# kritzler_shield.net
KiCad netlist of a schematic drawn in EAGLE
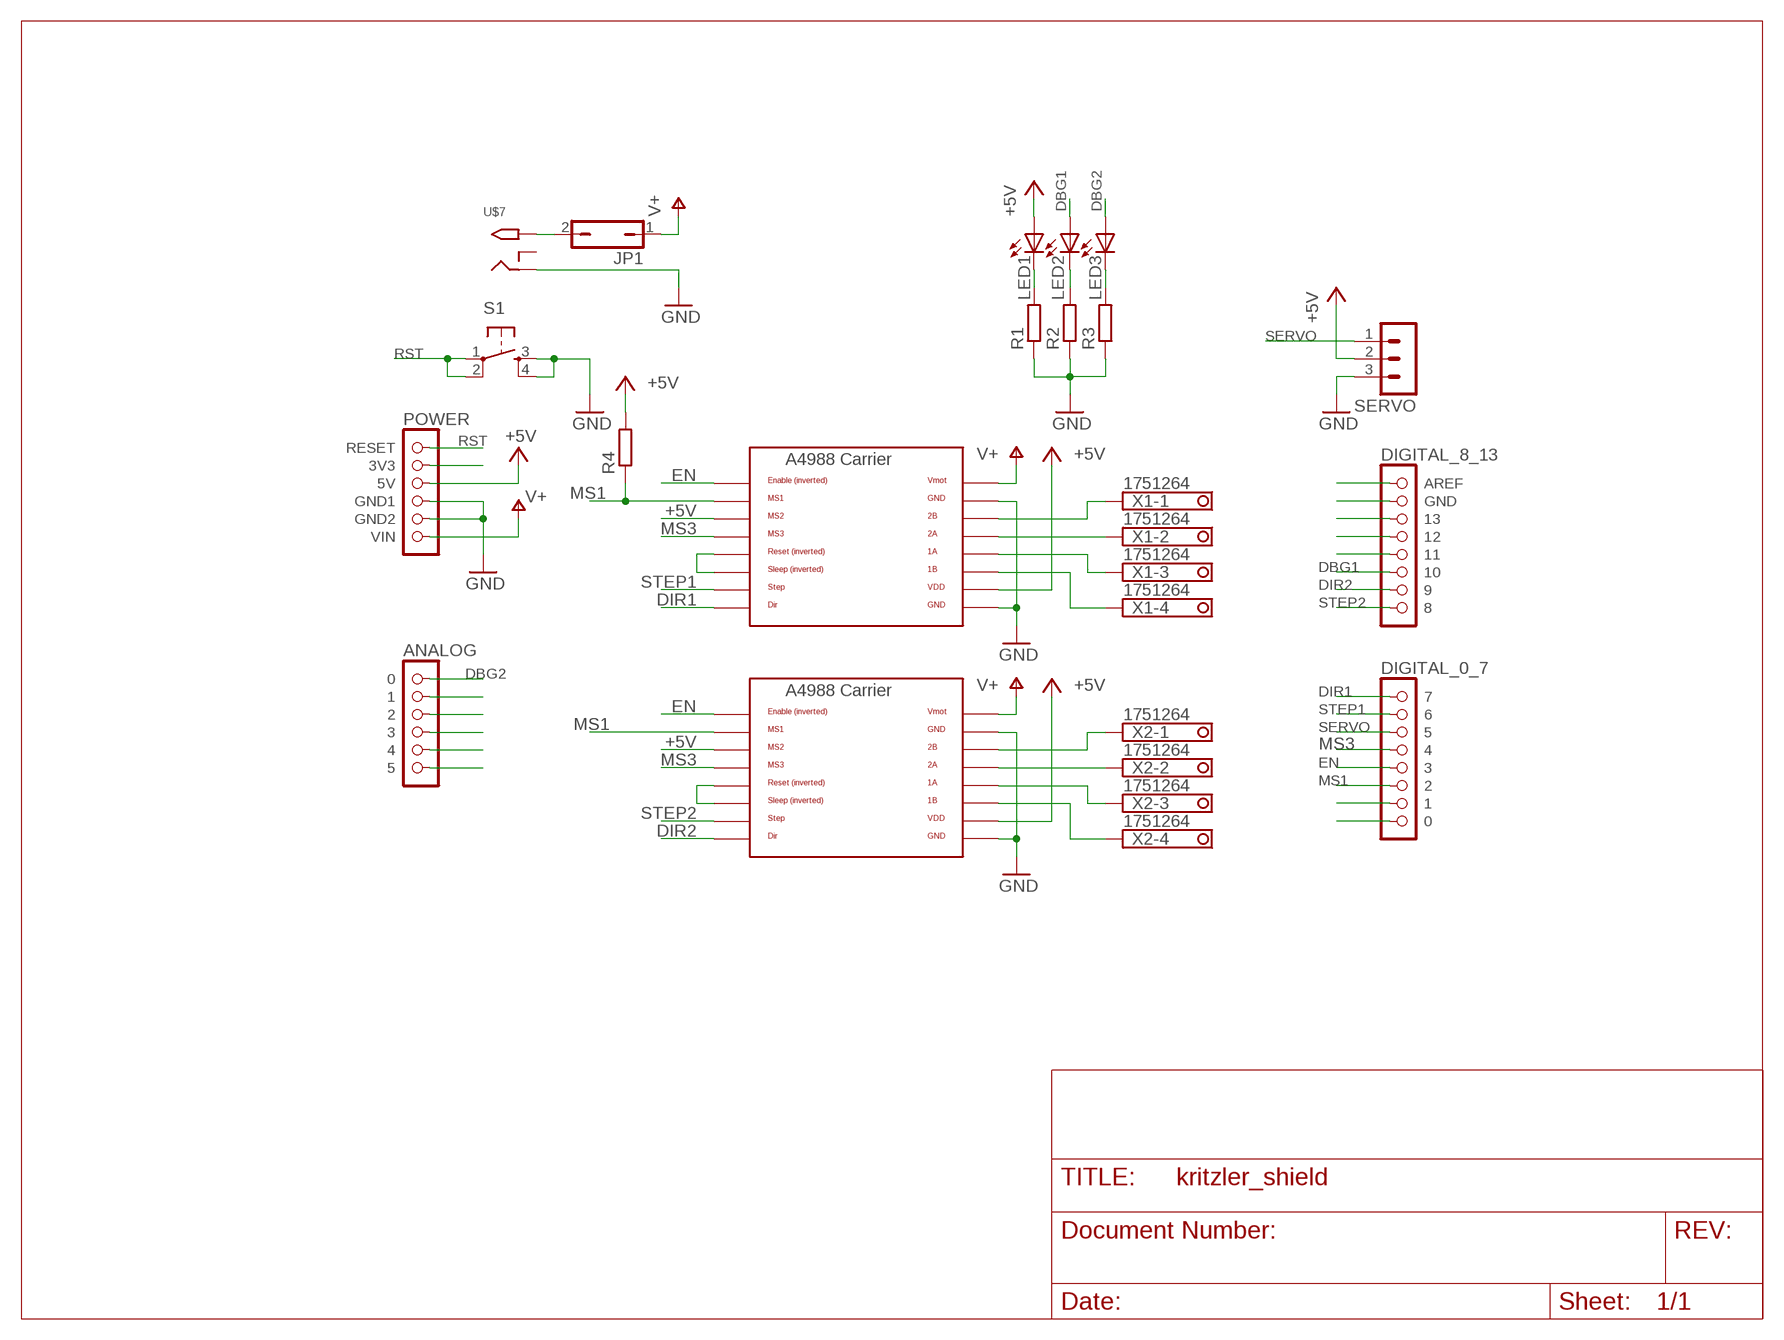
[diagram p0: schematic, sheet 1]

(export (version "E")
  (design (tool "Eeschema 10.0.6"))
  (components
    (comp (ref "JP1")
      (value "JP1Q")
      (footprint "eagle-import:JP1")
      (libsource (lib "eagle-import") (part "JP1Q"))
    )
    (comp (ref "LED1")
      (value "LED5MM")
      (footprint "eagle-import:LED5MM")
      (libsource (lib "eagle-import") (part "LED5MM"))
    )
    (comp (ref "LED2")
      (value "LED5MM")
      (footprint "eagle-import:LED5MM")
      (libsource (lib "eagle-import") (part "LED5MM"))
    )
    (comp (ref "LED3")
      (value "LED5MM")
      (footprint "eagle-import:LED5MM")
      (libsource (lib "eagle-import") (part "LED5MM"))
    )
    (comp (ref "R1")
      (value "R-EU_0207/10")
      (footprint "eagle-import:0207_10")
      (libsource (lib "eagle-import") (part "R-EU_0207/10"))
    )
    (comp (ref "R2")
      (value "R-EU_0207/10")
      (footprint "eagle-import:0207_10")
      (libsource (lib "eagle-import") (part "R-EU_0207/10"))
    )
    (comp (ref "R3")
      (value "R-EU_0207/10")
      (footprint "eagle-import:0207_10")
      (libsource (lib "eagle-import") (part "R-EU_0207/10"))
    )
    (comp (ref "R4")
      (value "R-EU_0207/10")
      (footprint "eagle-import:0207_10")
      (libsource (lib "eagle-import") (part "R-EU_0207/10"))
    )
    (comp (ref "S1")
      (value "TAC_SWITCHPTH")
      (footprint "eagle-import:TACTILE-PTH")
      (libsource (lib "eagle-import") (part "TAC_SWITCHPTH"))
    )
    (comp (ref "SERVO")
      (value "MA03-1")
      (footprint "eagle-import:MA03-1")
      (libsource (lib "eagle-import") (part "MA03-1"))
    )
    (comp (ref "U$1")
      (value "POWER")
      (footprint "eagle-import:1X06")
      (libsource (lib "eagle-import") (part "POWER"))
    )
    (comp (ref "U$2")
      (value "ANALOG")
      (footprint "eagle-import:1X06")
      (libsource (lib "eagle-import") (part "ANALOG"))
    )
    (comp (ref "U$3")
      (value "DIGITAL_0_7")
      (footprint "eagle-import:1X08")
      (libsource (lib "eagle-import") (part "DIGITAL_0_7"))
    )
    (comp (ref "U$4")
      (value "DIGITAL_8_13")
      (footprint "eagle-import:1X08")
      (libsource (lib "eagle-import") (part "DIGITAL_8_13"))
    )
    (comp (ref "U$5")
      (value "A4988BREAKOUT")
      (footprint "eagle-import:A4988BREAKOUT")
      (libsource (lib "eagle-import") (part "A4988BREAKOUT"))
    )
    (comp (ref "U$6")
      (value "A4988BREAKOUT")
      (footprint "eagle-import:A4988BREAKOUT")
      (libsource (lib "eagle-import") (part "A4988BREAKOUT"))
    )
    (comp (ref "U$7")
      (value "2.1MMJACKTHM")
      (footprint "eagle-import:PJ-102A")
      (libsource (lib "eagle-import") (part "2.1MMJACKTHM"))
    )
    (comp (ref "X1")
      (value "1751264")
      (footprint "eagle-import:1751264")
      (libsource (lib "eagle-import") (part "1751264"))
    )
    (comp (ref "X2")
      (value "1751264")
      (footprint "eagle-import:1751264")
      (libsource (lib "eagle-import") (part "1751264"))
    )
  )
  (nets
    (net (code "1") (name "+5V") (class "Default")
      (node (ref "LED1") (pin "A") (pinfunction "A_A") (pintype "passive"))
      (node (ref "R4") (pin "2") (pinfunction "2_2") (pintype "passive"))
      (node (ref "SERVO") (pin "2") (pinfunction "2_2") (pintype "passive"))
      (node (ref "U$1") (pin "3") (pinfunction "5V_3") (pintype "passive"))
      (node (ref "U$5") (pin "MS2") (pinfunction "MS2_MS2") (pintype "input"))
      (node (ref "U$5") (pin "VDD") (pinfunction "VDD_VDD") (pintype "power_in"))
      (node (ref "U$6") (pin "MS2") (pinfunction "MS2_MS2") (pintype "input"))
      (node (ref "U$6") (pin "VDD") (pinfunction "VDD_VDD") (pintype "power_in"))
    )
    (net (code "2") (name "/DBG1") (class "Default")
      (node (ref "LED2") (pin "A") (pinfunction "A_A") (pintype "passive"))
      (node (ref "U$4") (pin "6") (pinfunction "10_6") (pintype "passive"))
    )
    (net (code "3") (name "/DBG2") (class "Default")
      (node (ref "LED3") (pin "A") (pinfunction "A_A") (pintype "passive"))
      (node (ref "U$2") (pin "1") (pinfunction "0_1") (pintype "passive"))
    )
    (net (code "4") (name "/DIR1") (class "Default")
      (node (ref "U$3") (pin "1") (pinfunction "7_1") (pintype "passive"))
      (node (ref "U$5") (pin "DIR") (pinfunction "DIR_DIR") (pintype "input"))
    )
    (net (code "5") (name "/DIR2") (class "Default")
      (node (ref "U$4") (pin "7") (pinfunction "9_7") (pintype "passive"))
      (node (ref "U$6") (pin "DIR") (pinfunction "DIR_DIR") (pintype "input"))
    )
    (net (code "6") (name "/EN") (class "Default")
      (node (ref "U$3") (pin "5") (pinfunction "3_5") (pintype "passive"))
      (node (ref "U$5") (pin "EN") (pinfunction "EN_EN") (pintype "input"))
      (node (ref "U$6") (pin "EN") (pinfunction "EN_EN") (pintype "input"))
    )
    (net (code "7") (name "/MS1") (class "Default")
      (node (ref "R4") (pin "1") (pinfunction "1_1") (pintype "passive"))
      (node (ref "U$3") (pin "6") (pinfunction "2_6") (pintype "passive"))
      (node (ref "U$5") (pin "MS1") (pinfunction "MS1_MS1") (pintype "input"))
      (node (ref "U$6") (pin "MS1") (pinfunction "MS1_MS1") (pintype "input"))
    )
    (net (code "8") (name "/MS3") (class "Default")
      (node (ref "U$3") (pin "4") (pinfunction "4_4") (pintype "passive"))
      (node (ref "U$5") (pin "MS3") (pinfunction "MS3_MS3") (pintype "input"))
      (node (ref "U$6") (pin "MS3") (pinfunction "MS3_MS3") (pintype "input"))
    )
    (net (code "9") (name "/RST") (class "Default")
      (node (ref "S1") (pin "1") (pinfunction "1_1") (pintype "passive"))
      (node (ref "S1") (pin "2") (pinfunction "2_2") (pintype "passive"))
      (node (ref "U$1") (pin "1") (pinfunction "RESET_1") (pintype "passive"))
    )
    (net (code "10") (name "/SERVO") (class "Default")
      (node (ref "SERVO") (pin "1") (pinfunction "1_1") (pintype "passive"))
      (node (ref "U$3") (pin "3") (pinfunction "5_3") (pintype "passive"))
    )
    (net (code "11") (name "/STEP1") (class "Default")
      (node (ref "U$3") (pin "2") (pinfunction "6_2") (pintype "passive"))
      (node (ref "U$5") (pin "STEP") (pinfunction "STEP_STEP") (pintype "input"))
    )
    (net (code "12") (name "/STEP2") (class "Default")
      (node (ref "U$4") (pin "8") (pinfunction "8_8") (pintype "passive"))
      (node (ref "U$6") (pin "STEP") (pinfunction "STEP_STEP") (pintype "input"))
    )
    (net (code "13") (name "GND") (class "Default")
      (node (ref "R1") (pin "1") (pinfunction "1_1") (pintype "passive"))
      (node (ref "R2") (pin "1") (pinfunction "1_1") (pintype "passive"))
      (node (ref "R3") (pin "1") (pinfunction "1_1") (pintype "passive"))
      (node (ref "S1") (pin "3") (pinfunction "3_3") (pintype "passive"))
      (node (ref "S1") (pin "4") (pinfunction "4_4") (pintype "passive"))
      (node (ref "SERVO") (pin "3") (pinfunction "3_3") (pintype "passive"))
      (node (ref "U$1") (pin "4") (pinfunction "GND1_4") (pintype "passive"))
      (node (ref "U$1") (pin "5") (pinfunction "GND2_5") (pintype "passive"))
      (node (ref "U$5") (pin "GND") (pinfunction "GND_GND") (pintype "power_in"))
      (node (ref "U$5") (pin "GND@0") (pinfunction "GND_GND@0") (pintype "power_in"))
      (node (ref "U$6") (pin "GND") (pinfunction "GND_GND") (pintype "power_in"))
      (node (ref "U$6") (pin "GND@0") (pinfunction "GND_GND@0") (pintype "power_in"))
      (node (ref "U$7") (pin "RING") (pinfunction "RING_RING") (pintype "bidirectional"))
    )
    (net (code "14") (name "Net-(JP1-Pad2)") (class "Default")
      (node (ref "JP1") (pin "2") (pinfunction "2_2") (pintype "passive"))
      (node (ref "U$7") (pin "TIP") (pinfunction "TIP_TIP") (pintype "bidirectional"))
    )
    (net (code "15") (name "Net-(LED1-C)") (class "Default")
      (node (ref "LED1") (pin "K") (pinfunction "C_K") (pintype "passive"))
      (node (ref "R1") (pin "2") (pinfunction "2_2") (pintype "passive"))
    )
    (net (code "16") (name "Net-(LED2-C)") (class "Default")
      (node (ref "LED2") (pin "K") (pinfunction "C_K") (pintype "passive"))
      (node (ref "R2") (pin "2") (pinfunction "2_2") (pintype "passive"))
    )
    (net (code "17") (name "Net-(LED3-C)") (class "Default")
      (node (ref "LED3") (pin "K") (pinfunction "C_K") (pintype "passive"))
      (node (ref "R3") (pin "2") (pinfunction "2_2") (pintype "passive"))
    )
    (net (code "18") (name "Net-(U$5-SLEEP)") (class "Default")
      (node (ref "U$5") (pin "RST") (pinfunction "RST_RST") (pintype "input"))
      (node (ref "U$5") (pin "SLP") (pinfunction "SLEEP_SLP") (pintype "input"))
    )
    (net (code "19") (name "Net-(U$6-SLEEP)") (class "Default")
      (node (ref "U$6") (pin "RST") (pinfunction "RST_RST") (pintype "input"))
      (node (ref "U$6") (pin "SLP") (pinfunction "SLEEP_SLP") (pintype "input"))
    )
    (net (code "20") (name "Net-(X1A-K)") (class "Default")
      (node (ref "U$5") (pin "2B") (pinfunction "2B_2B") (pintype "output"))
      (node (ref "X1") (pin "1") (pinfunction "K_1") (pintype "passive"))
    )
    (net (code "21") (name "Net-(X1B-K)") (class "Default")
      (node (ref "U$5") (pin "2A") (pinfunction "2A_2A") (pintype "output"))
      (node (ref "X1") (pin "2") (pinfunction "K_2") (pintype "passive"))
    )
    (net (code "22") (name "Net-(X1C-K)") (class "Default")
      (node (ref "U$5") (pin "1A") (pinfunction "1A_1A") (pintype "output"))
      (node (ref "X1") (pin "3") (pinfunction "K_3") (pintype "passive"))
    )
    (net (code "23") (name "Net-(X1D-K)") (class "Default")
      (node (ref "U$5") (pin "1B") (pinfunction "1B_1B") (pintype "output"))
      (node (ref "X1") (pin "4") (pinfunction "K_4") (pintype "passive"))
    )
    (net (code "24") (name "Net-(X2A-K)") (class "Default")
      (node (ref "U$6") (pin "2B") (pinfunction "2B_2B") (pintype "output"))
      (node (ref "X2") (pin "1") (pinfunction "K_1") (pintype "passive"))
    )
    (net (code "25") (name "Net-(X2B-K)") (class "Default")
      (node (ref "U$6") (pin "2A") (pinfunction "2A_2A") (pintype "output"))
      (node (ref "X2") (pin "2") (pinfunction "K_2") (pintype "passive"))
    )
    (net (code "26") (name "Net-(X2C-K)") (class "Default")
      (node (ref "U$6") (pin "1A") (pinfunction "1A_1A") (pintype "output"))
      (node (ref "X2") (pin "3") (pinfunction "K_3") (pintype "passive"))
    )
    (net (code "27") (name "Net-(X2D-K)") (class "Default")
      (node (ref "U$6") (pin "1B") (pinfunction "1B_1B") (pintype "output"))
      (node (ref "X2") (pin "4") (pinfunction "K_4") (pintype "passive"))
    )
    (net (code "28") (name "V+") (class "Default")
      (node (ref "JP1") (pin "1") (pinfunction "1_1") (pintype "passive"))
      (node (ref "U$1") (pin "6") (pinfunction "VIN_6") (pintype "passive"))
      (node (ref "U$5") (pin "VMOT") (pinfunction "VMOT_VMOT") (pintype "power_in"))
      (node (ref "U$6") (pin "VMOT") (pinfunction "VMOT_VMOT") (pintype "power_in"))
    )
    (net (code "29") (name "unconnected-(U$1-3V3-Pad2)") (class "Default")
      (node (ref "U$1") (pin "2") (pinfunction "3V3_2") (pintype "passive"))
    )
    (net (code "30") (name "unconnected-(U$2-1-Pad2)") (class "Default")
      (node (ref "U$2") (pin "2") (pinfunction "1_2") (pintype "passive"))
    )
    (net (code "31") (name "unconnected-(U$2-2-Pad3)") (class "Default")
      (node (ref "U$2") (pin "3") (pinfunction "2_3") (pintype "passive"))
    )
    (net (code "32") (name "unconnected-(U$2-3-Pad4)") (class "Default")
      (node (ref "U$2") (pin "4") (pinfunction "3_4") (pintype "passive"))
    )
    (net (code "33") (name "unconnected-(U$2-4-Pad5)") (class "Default")
      (node (ref "U$2") (pin "5") (pinfunction "4_5") (pintype "passive"))
    )
    (net (code "34") (name "unconnected-(U$2-5-Pad6)") (class "Default")
      (node (ref "U$2") (pin "6") (pinfunction "5_6") (pintype "passive"))
    )
    (net (code "35") (name "unconnected-(U$3-0-Pad8)") (class "Default")
      (node (ref "U$3") (pin "8") (pinfunction "0_8") (pintype "passive"))
    )
    (net (code "36") (name "unconnected-(U$3-1-Pad7)") (class "Default")
      (node (ref "U$3") (pin "7") (pinfunction "1_7") (pintype "passive"))
    )
    (net (code "37") (name "unconnected-(U$4-11-Pad5)") (class "Default")
      (node (ref "U$4") (pin "5") (pinfunction "11_5") (pintype "passive"))
    )
    (net (code "38") (name "unconnected-(U$4-12-Pad4)") (class "Default")
      (node (ref "U$4") (pin "4") (pinfunction "12_4") (pintype "passive"))
    )
    (net (code "39") (name "unconnected-(U$4-13-Pad3)") (class "Default")
      (node (ref "U$4") (pin "3") (pinfunction "13_3") (pintype "passive"))
    )
    (net (code "40") (name "unconnected-(U$4-AREF-Pad1)") (class "Default")
      (node (ref "U$4") (pin "1") (pinfunction "AREF_1") (pintype "passive"))
    )
    (net (code "41") (name "unconnected-(U$4-GND-Pad2)") (class "Default")
      (node (ref "U$4") (pin "2") (pinfunction "GND_2") (pintype "passive"))
    )
    (net (code "42") (name "unconnected-(U$7-PadRING_SW)") (class "Default")
      (node (ref "U$7") (pin "RING_SW") (pinfunction "RING_SW_RING_SW") (pintype "bidirectional"))
    )
  )
)
